# SIM.net
KiCad netlist of a schematic drawn in Altium Designer
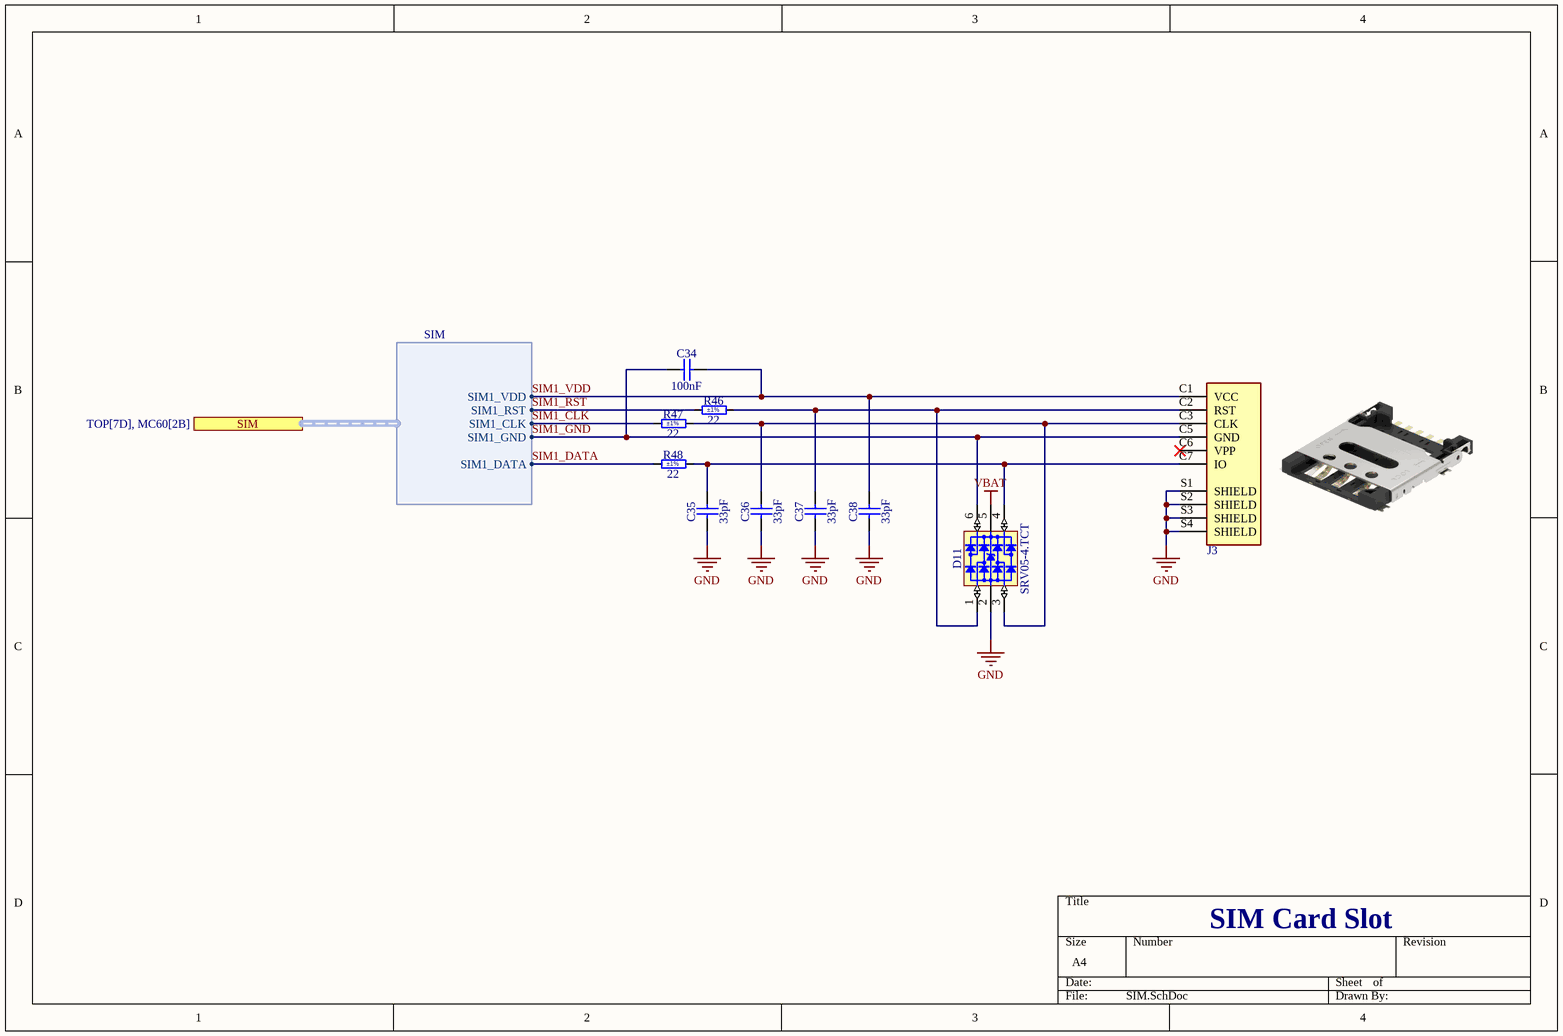
[diagram p0: SIM.SchDoc]

(export (version "E")
  (design (tool "Eeschema 10.0.6"))
  (components
    (comp (ref "C34")
      (value "100nF")
      (footprint "CAPC1608X87N")
      (description "Non-polarised capacitor")
      (fields
        (field (name "PART NUMBER") "CC0603_100NF_50V_10%_X7R")
        (field (name "VOLTAGE") "50V")
        (field (name "AUTHOR") "CERN DEM JLC")
      )
      (libsource (lib "Capacitors") (part "Capacitor - non polarized"))
    )
    (comp (ref "C35")
      (value "33pF")
      (footprint "CAPC1608X87N")
      (description "Non-polarised capacitor")
      (fields
        (field (name "PART NUMBER") "CC0603_33PF_50V_5%_NP0")
        (field (name "VOLTAGE") "50V")
        (field (name "AUTHOR") "CERN DEM JLC")
      )
      (libsource (lib "Capacitors") (part "Capacitor - non polarized"))
    )
    (comp (ref "C36")
      (value "33pF")
      (footprint "CAPC1608X87N")
      (description "Non-polarised capacitor")
      (fields
        (field (name "PART NUMBER") "CC0603_33PF_50V_5%_NP0")
        (field (name "VOLTAGE") "50V")
        (field (name "AUTHOR") "CERN DEM JLC")
      )
      (libsource (lib "Capacitors") (part "Capacitor - non polarized"))
    )
    (comp (ref "C37")
      (value "33pF")
      (footprint "CAPC1608X87N")
      (description "Non-polarised capacitor")
      (fields
        (field (name "PART NUMBER") "CC0603_33PF_50V_5%_NP0")
        (field (name "VOLTAGE") "50V")
        (field (name "AUTHOR") "CERN DEM JLC")
      )
      (libsource (lib "Capacitors") (part "Capacitor - non polarized"))
    )
    (comp (ref "C38")
      (value "33pF")
      (footprint "CAPC1608X87N")
      (description "Non-polarised capacitor")
      (fields
        (field (name "PART NUMBER") "CC0603_33PF_50V_5%_NP0")
        (field (name "VOLTAGE") "50V")
        (field (name "AUTHOR") "CERN DEM JLC")
      )
      (libsource (lib "Capacitors") (part "Capacitor - non polarized"))
    )
    (comp (ref "D11")
      (value "SRV05-4.TCT")
      (footprint "SOT95P280X145-6N")
      (description "RailClamps Low Capacitance TVS Diode Array")
      (fields
        (field (name "POWER") "300W")
        (field (name "MANUFACTURER") "SEMTECH")
        (field (name "AUTHOR") "CERN DEM JLC")
      )
      (libsource (lib "ICs And Semiconductors") (part "SRV05-4"))
    )
    (comp (ref "J3")
      (value "SIM8060-6-0-14-00-A")
      (footprint "GCT_SIM8060-6-0-14-00-A")
      (description "6 Position Card Connector NANO SIM Surface Mount, Right Angle Gold")
      (fields
        (field (name "MF") "Global Connector Technology")
        (field (name "PART NUMBER") "GCT_SIM8060-6-0-14-00-A")
        (field (name "AUTHOR") "Xusniyor")
      )
      (libsource (lib "Connectors") (part "GCT_SIM8060-6-0-14-00-A"))
    )
    (comp (ref "R46")
      (value "22")
      (footprint "RESC1608X55N")
      (description "Resistor - 1%")
      (fields
        (field (name "TOLERANCE") "±1%")
        (field (name "PART NUMBER") "R0603_22R_1%_0.1W_100PPM")
        (field (name "POWER") "0.1W")
        (field (name "AUTHOR") "CERN DEM JLC")
      )
      (libsource (lib "Resistors") (part "Resistor - 1%"))
    )
    (comp (ref "R47")
      (value "22")
      (footprint "RESC1608X55N")
      (description "Resistor - 1%")
      (fields
        (field (name "TOLERANCE") "±1%")
        (field (name "PART NUMBER") "R0603_22R_1%_0.1W_100PPM")
        (field (name "POWER") "0.1W")
        (field (name "AUTHOR") "CERN DEM JLC")
      )
      (libsource (lib "Resistors") (part "Resistor - 1%"))
    )
    (comp (ref "R48")
      (value "22")
      (footprint "RESC1608X55N")
      (description "Resistor - 1%")
      (fields
        (field (name "TOLERANCE") "±1%")
        (field (name "PART NUMBER") "R0603_22R_1%_0.1W_100PPM")
        (field (name "POWER") "0.1W")
        (field (name "AUTHOR") "CERN DEM JLC")
      )
      (libsource (lib "Resistors") (part "Resistor - 1%"))
    )
  )
  (nets
    (net (code "2") (name "/SIM1_CLK") (class "Default")
      (node (ref "R47") (pin "1") (pinfunction "1_1") (pintype "passive"))
    )
    (net (code "3") (name "/SIM1_DATA") (class "Default")
      (node (ref "R48") (pin "1") (pinfunction "1_1") (pintype "passive"))
    )
    (net (code "4") (name "/SIM1_GND") (class "Default")
      (node (ref "C34") (pin "1") (pinfunction "1_1") (pintype "passive"))
      (node (ref "D11") (pin "6") (pinfunction "I/O4_6") (pintype "bidirectional"))
      (node (ref "J3") (pin "C5") (pinfunction "GND_C5") (pintype "passive"))
    )
    (net (code "5") (name "/SIM1_RST") (class "Default")
      (node (ref "R46") (pin "1") (pinfunction "1_1") (pintype "passive"))
    )
    (net (code "6") (name "/SIM1_VDD") (class "Default")
      (node (ref "C34") (pin "2") (pinfunction "2_2") (pintype "passive"))
      (node (ref "C38") (pin "2") (pinfunction "2_2") (pintype "passive"))
      (node (ref "J3") (pin "C1") (pinfunction "VCC_C1") (pintype "passive"))
    )
    (net (code "8") (name "GND") (class "Default")
      (node (ref "C35") (pin "1") (pinfunction "1_1") (pintype "passive"))
      (node (ref "C36") (pin "1") (pinfunction "1_1") (pintype "passive"))
      (node (ref "C37") (pin "1") (pinfunction "1_1") (pintype "passive"))
      (node (ref "C38") (pin "1") (pinfunction "1_1") (pintype "passive"))
      (node (ref "D11") (pin "2") (pinfunction "GND_2") (pintype "power_in"))
      (node (ref "J3") (pin "S1") (pinfunction "SHIELD_S1") (pintype "passive"))
      (node (ref "J3") (pin "S2") (pinfunction "SHIELD_S2") (pintype "passive"))
      (node (ref "J3") (pin "S3") (pinfunction "SHIELD_S3") (pintype "passive"))
      (node (ref "J3") (pin "S4") (pinfunction "SHIELD_S4") (pintype "passive"))
    )
    (net (code "9") (name "Net-(D11-I{slash}O1)") (class "Default")
      (node (ref "C37") (pin "2") (pinfunction "2_2") (pintype "passive"))
      (node (ref "D11") (pin "1") (pinfunction "I/O1_1") (pintype "bidirectional"))
      (node (ref "J3") (pin "C2") (pinfunction "RST_C2") (pintype "passive"))
      (node (ref "R46") (pin "2") (pinfunction "2_2") (pintype "passive"))
    )
    (net (code "10") (name "Net-(D11-I{slash}O2)") (class "Default")
      (node (ref "C36") (pin "2") (pinfunction "2_2") (pintype "passive"))
      (node (ref "D11") (pin "3") (pinfunction "I/O2_3") (pintype "bidirectional"))
      (node (ref "J3") (pin "C3") (pinfunction "CLK_C3") (pintype "passive"))
      (node (ref "R47") (pin "2") (pinfunction "2_2") (pintype "passive"))
    )
    (net (code "11") (name "Net-(D11-I{slash}O3)") (class "Default")
      (node (ref "C35") (pin "2") (pinfunction "2_2") (pintype "passive"))
      (node (ref "D11") (pin "4") (pinfunction "I/O3_4") (pintype "bidirectional"))
      (node (ref "J3") (pin "C7") (pinfunction "IO_C7") (pintype "passive"))
      (node (ref "R48") (pin "2") (pinfunction "2_2") (pintype "passive"))
    )
    (net (code "12") (name "VBAT") (class "Default")
      (node (ref "D11") (pin "5") (pinfunction "VBUS_5") (pintype "power_in"))
    )
    (net (code "13") (name "unconnected-(J3-VPP-PadC6)") (class "Default")
      (node (ref "J3") (pin "C6") (pinfunction "VPP_C6") (pintype "passive+no_connect"))
    )
  )
)
